# Shels_System_Bmduino.net
KiCad netlist of a schematic drawn in Altium Designer
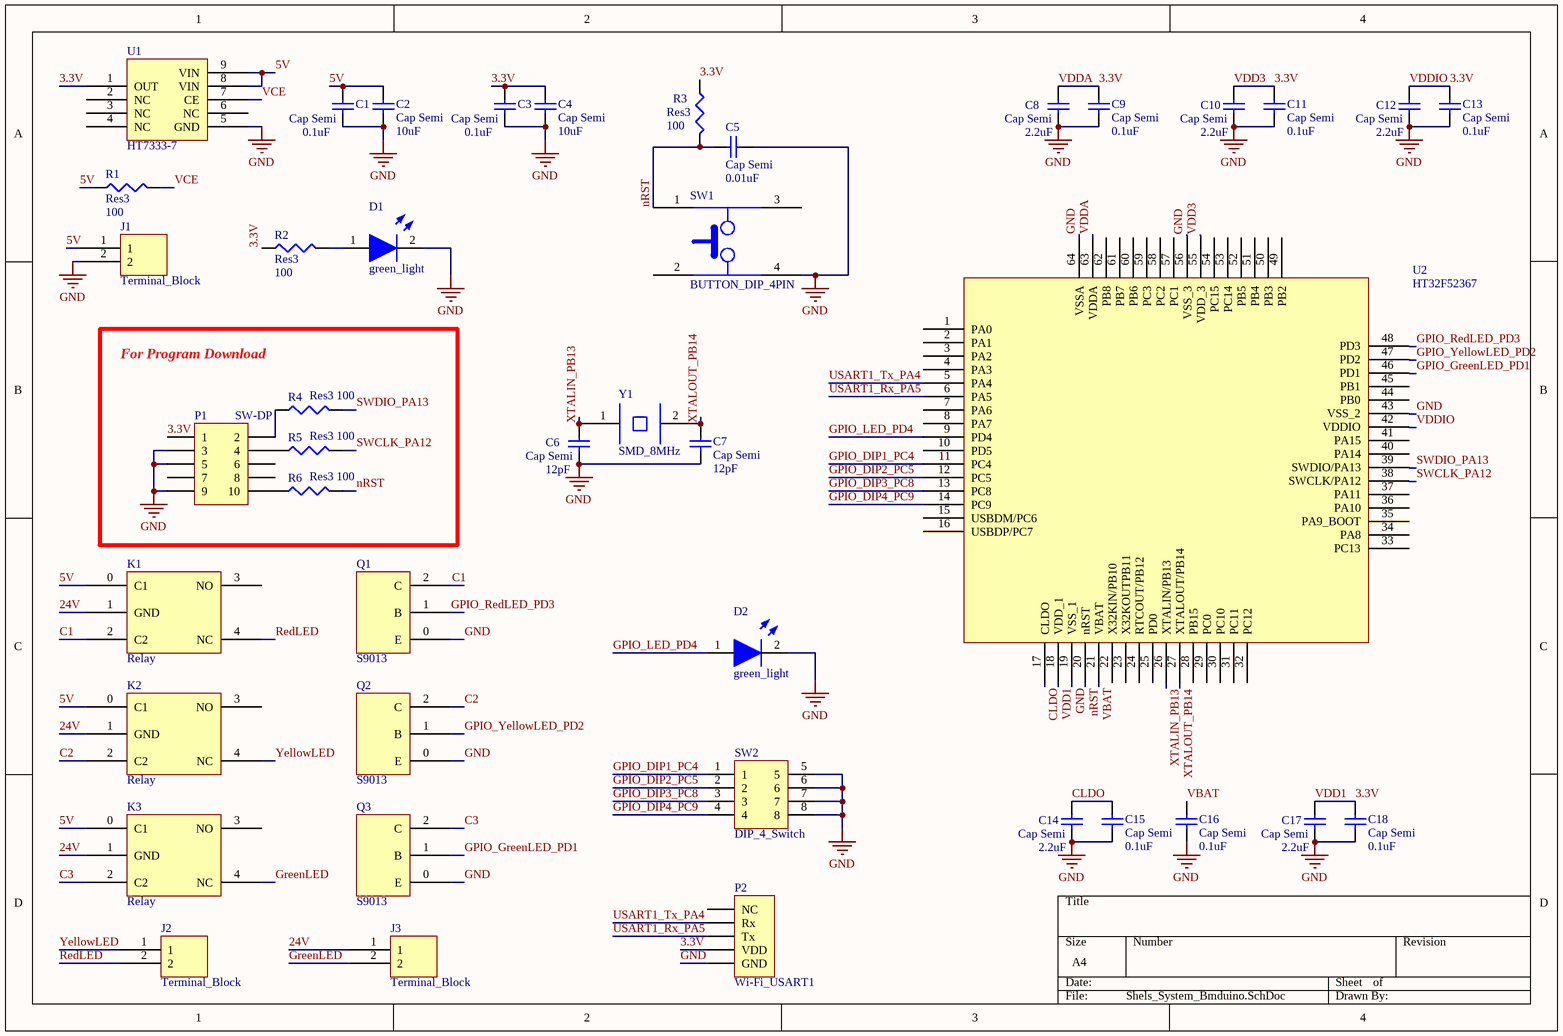
[diagram p0: Shels_System_Bmduino.SchDoc]

(export (version "E")
  (design (tool "Eeschema 10.0.6"))
  (components
    (comp (ref "C1")
      (value "Cap Semi")
      (footprint "1608[0603]")
      (description "Capacitor (Semiconductor SIM Model)")
      (fields (field (name "ALTIUM_VALUE") "0.1uF") (field (name "PUBLISHER") "Altium Limited"))
      (libsource (lib "Miscellaneous Devices") (part "Cap Semi"))
    )
    (comp (ref "C2")
      (value "Cap Semi")
      (footprint "1608[0603]")
      (description "Capacitor (Semiconductor SIM Model)")
      (fields (field (name "ALTIUM_VALUE") "10uF") (field (name "PUBLISHER") "Altium Limited"))
      (libsource (lib "Miscellaneous Devices") (part "Cap Semi"))
    )
    (comp (ref "C3")
      (value "Cap Semi")
      (footprint "1608[0603]")
      (description "Capacitor (Semiconductor SIM Model)")
      (fields (field (name "ALTIUM_VALUE") "0.1uF") (field (name "PUBLISHER") "Altium Limited"))
      (libsource (lib "Miscellaneous Devices") (part "Cap Semi"))
    )
    (comp (ref "C4")
      (value "Cap Semi")
      (footprint "1608[0603]")
      (description "Capacitor (Semiconductor SIM Model)")
      (fields (field (name "ALTIUM_VALUE") "10uF") (field (name "PUBLISHER") "Altium Limited"))
      (libsource (lib "Miscellaneous Devices") (part "Cap Semi"))
    )
    (comp (ref "C5")
      (value "Cap Semi")
      (footprint "1608[0603]")
      (description "Capacitor (Semiconductor SIM Model)")
      (fields (field (name "ALTIUM_VALUE") "0.01uF") (field (name "PUBLISHER") "Altium Limited"))
      (libsource (lib "Miscellaneous Devices") (part "Cap Semi"))
    )
    (comp (ref "C6")
      (value "Cap Semi")
      (footprint "1608[0603]")
      (description "Capacitor (Semiconductor SIM Model)")
      (fields (field (name "ALTIUM_VALUE") "12pF") (field (name "PUBLISHER") "Altium Limited"))
      (libsource (lib "Miscellaneous Devices") (part "Cap Semi"))
    )
    (comp (ref "C7")
      (value "Cap Semi")
      (footprint "1608[0603]")
      (description "Capacitor (Semiconductor SIM Model)")
      (fields (field (name "ALTIUM_VALUE") "12pF") (field (name "PUBLISHER") "Altium Limited"))
      (libsource (lib "Miscellaneous Devices") (part "Cap Semi"))
    )
    (comp (ref "C8")
      (value "Cap Semi")
      (footprint "1608[0603]")
      (description "Capacitor (Semiconductor SIM Model)")
      (fields (field (name "ALTIUM_VALUE") "2.2uF") (field (name "PUBLISHER") "Altium Limited"))
      (libsource (lib "Miscellaneous Devices") (part "Cap Semi"))
    )
    (comp (ref "C9")
      (value "Cap Semi")
      (footprint "1608[0603]")
      (description "Capacitor (Semiconductor SIM Model)")
      (fields (field (name "ALTIUM_VALUE") "0.1uF") (field (name "PUBLISHER") "Altium Limited"))
      (libsource (lib "Miscellaneous Devices") (part "Cap Semi"))
    )
    (comp (ref "C10")
      (value "Cap Semi")
      (footprint "1608[0603]")
      (description "Capacitor (Semiconductor SIM Model)")
      (fields (field (name "ALTIUM_VALUE") "2.2uF") (field (name "PUBLISHER") "Altium Limited"))
      (libsource (lib "Miscellaneous Devices") (part "Cap Semi"))
    )
    (comp (ref "C11")
      (value "Cap Semi")
      (footprint "1608[0603]")
      (description "Capacitor (Semiconductor SIM Model)")
      (fields (field (name "ALTIUM_VALUE") "0.1uF") (field (name "PUBLISHER") "Altium Limited"))
      (libsource (lib "Miscellaneous Devices") (part "Cap Semi"))
    )
    (comp (ref "C12")
      (value "Cap Semi")
      (footprint "1608[0603]")
      (description "Capacitor (Semiconductor SIM Model)")
      (fields (field (name "ALTIUM_VALUE") "2.2uF") (field (name "PUBLISHER") "Altium Limited"))
      (libsource (lib "Miscellaneous Devices") (part "Cap Semi"))
    )
    (comp (ref "C13")
      (value "Cap Semi")
      (footprint "1608[0603]")
      (description "Capacitor (Semiconductor SIM Model)")
      (fields (field (name "ALTIUM_VALUE") "0.1uF") (field (name "PUBLISHER") "Altium Limited"))
      (libsource (lib "Miscellaneous Devices") (part "Cap Semi"))
    )
    (comp (ref "C14")
      (value "Cap Semi")
      (footprint "1608[0603]")
      (description "Capacitor (Semiconductor SIM Model)")
      (fields (field (name "ALTIUM_VALUE") "2.2uF") (field (name "PUBLISHER") "Altium Limited"))
      (libsource (lib "Miscellaneous Devices") (part "Cap Semi"))
    )
    (comp (ref "C15")
      (value "Cap Semi")
      (footprint "1608[0603]")
      (description "Capacitor (Semiconductor SIM Model)")
      (fields (field (name "ALTIUM_VALUE") "0.1uF") (field (name "PUBLISHER") "Altium Limited"))
      (libsource (lib "Miscellaneous Devices") (part "Cap Semi"))
    )
    (comp (ref "C16")
      (value "Cap Semi")
      (footprint "1608[0603]")
      (description "Capacitor (Semiconductor SIM Model)")
      (fields (field (name "ALTIUM_VALUE") "0.1uF") (field (name "PUBLISHER") "Altium Limited"))
      (libsource (lib "Miscellaneous Devices") (part "Cap Semi"))
    )
    (comp (ref "C17")
      (value "Cap Semi")
      (footprint "1608[0603]")
      (description "Capacitor (Semiconductor SIM Model)")
      (fields (field (name "ALTIUM_VALUE") "2.2uF") (field (name "PUBLISHER") "Altium Limited"))
      (libsource (lib "Miscellaneous Devices") (part "Cap Semi"))
    )
    (comp (ref "C18")
      (value "Cap Semi")
      (footprint "1608[0603]")
      (description "Capacitor (Semiconductor SIM Model)")
      (fields (field (name "ALTIUM_VALUE") "0.1uF") (field (name "PUBLISHER") "Altium Limited"))
      (libsource (lib "Miscellaneous Devices") (part "Cap Semi"))
    )
    (comp (ref "D1")
      (value "green_light")
      (footprint "LED_Green")
      (libsource (lib "Lab_share") (part "LED_Green"))
    )
    (comp (ref "D2")
      (value "green_light")
      (footprint "LED_Green")
      (libsource (lib "Lab_share") (part "LED_Green"))
    )
    (comp (ref "J1")
      (value "Terminal_Block")
      (footprint "terminal block")
      (libsource (lib "Lab_share") (part "Terminal Block"))
    )
    (comp (ref "J2")
      (value "Terminal_Block")
      (footprint "terminal block")
      (libsource (lib "Lab_share") (part "Terminal Block"))
    )
    (comp (ref "J3")
      (value "Terminal_Block")
      (footprint "terminal block")
      (libsource (lib "Lab_share") (part "Terminal Block"))
    )
    (comp (ref "K1") (value "Relay") (footprint "Relay") (libsource (lib "Lab_share") (part "Relay")))
    (comp (ref "K2") (value "Relay") (footprint "Relay") (libsource (lib "Lab_share") (part "Relay")))
    (comp (ref "K3") (value "Relay") (footprint "Relay") (libsource (lib "Lab_share") (part "Relay")))
    (comp (ref "P1")
      (value "SW-DP")
      (footprint "HDR2X5")
      (description "Header, 5-Pin, Dual row")
      (fields (field (name "PUBLISHER") "Altium Limited"))
      (libsource (lib "Miscellaneous Connectors") (part "Header 5X2"))
    )
    (comp (ref "P2")
      (value "Wi-Fi_USART1")
      (footprint "HDR1X5")
      (description "Header, 5-Pin")
      (fields (field (name "PUBLISHER") "Altium Limited"))
      (libsource (lib "Miscellaneous Connectors") (part "Header 5"))
    )
    (comp (ref "Q1") (value "S9013") (footprint "S9013") (libsource (lib "Lab_share") (part "S9013")))
    (comp (ref "Q2") (value "S9013") (footprint "S9013") (libsource (lib "Lab_share") (part "S9013")))
    (comp (ref "Q3") (value "S9013") (footprint "S9013") (libsource (lib "Lab_share") (part "S9013")))
    (comp (ref "R1")
      (value "Res3")
      (footprint "J1-0603")
      (description "Resistor")
      (fields (field (name "ALTIUM_VALUE") "100") (field (name "PUBLISHER") "Altium Limited"))
      (libsource (lib "Miscellaneous Devices") (part "Res3"))
    )
    (comp (ref "R2")
      (value "Res3")
      (footprint "J1-0603")
      (description "Resistor")
      (fields (field (name "ALTIUM_VALUE") "100") (field (name "PUBLISHER") "Altium Limited"))
      (libsource (lib "Miscellaneous Devices") (part "Res3"))
    )
    (comp (ref "R3")
      (value "Res3")
      (footprint "J1-0603")
      (description "Resistor")
      (fields (field (name "ALTIUM_VALUE") "100") (field (name "PUBLISHER") "Altium Limited"))
      (libsource (lib "Miscellaneous Devices") (part "Res3"))
    )
    (comp (ref "R4")
      (value "Res3")
      (footprint "J1-0603")
      (description "Resistor")
      (fields (field (name "ALTIUM_VALUE") "100") (field (name "PUBLISHER") "Altium Limited"))
      (libsource (lib "Miscellaneous Devices") (part "Res3"))
    )
    (comp (ref "R5")
      (value "Res3")
      (footprint "J1-0603")
      (description "Resistor")
      (fields (field (name "ALTIUM_VALUE") "100") (field (name "PUBLISHER") "Altium Limited"))
      (libsource (lib "Miscellaneous Devices") (part "Res3"))
    )
    (comp (ref "R6")
      (value "Res3")
      (footprint "J1-0603")
      (description "Resistor")
      (fields (field (name "ALTIUM_VALUE") "100") (field (name "PUBLISHER") "Altium Limited"))
      (libsource (lib "Miscellaneous Devices") (part "Res3"))
    )
    (comp (ref "SW1")
      (value "BUTTON_DIP_4PIN")
      (footprint "Push_Button")
      (libsource (lib "Lab_share") (part "Push_Button"))
    )
    (comp (ref "SW2")
      (value "DIP_4_Switch")
      (footprint "D_Switch_4")
      (libsource (lib "Lab_share") (part "Switch_D_4"))
    )
    (comp (ref "U1") (value "HT7333-7") (footprint "HT7333") (libsource (lib "Lab_share") (part "HT7333")))
    (comp (ref "U2")
      (value "HT32F52367")
      (footprint "HT32H52367")
      (libsource (lib "Lab_share") (part "HT32F52367"))
    )
    (comp (ref "Y1")
      (value "SMD_8MHz")
      (footprint "Quartz-Crystal-8MHz")
      (libsource (lib "Lab_share") (part "Quartz_Crystal_8MHz"))
    )
  )
  (nets
    (net (code "1") (name "/3.3V") (class "Default")
      (node (ref "C10") (pin "1") (pinfunction "1_1") (pintype "passive"))
      (node (ref "C11") (pin "2") (pinfunction "2_2") (pintype "passive"))
      (node (ref "C12") (pin "1") (pinfunction "1_1") (pintype "passive"))
      (node (ref "C13") (pin "2") (pinfunction "2_2") (pintype "passive"))
      (node (ref "C17") (pin "1") (pinfunction "1_1") (pintype "passive"))
      (node (ref "C18") (pin "2") (pinfunction "2_2") (pintype "passive"))
      (node (ref "C3") (pin "2") (pinfunction "2_2") (pintype "passive"))
      (node (ref "C4") (pin "2") (pinfunction "2_2") (pintype "passive"))
      (node (ref "C8") (pin "1") (pinfunction "1_1") (pintype "passive"))
      (node (ref "C9") (pin "2") (pinfunction "2_2") (pintype "passive"))
      (node (ref "P1") (pin "1") (pinfunction "1_1") (pintype "passive"))
      (node (ref "P2") (pin "4") (pinfunction "VDD_4") (pintype "passive"))
      (node (ref "R2") (pin "1") (pinfunction "1_1") (pintype "passive"))
      (node (ref "R3") (pin "1") (pinfunction "1_1") (pintype "passive"))
      (node (ref "U1") (pin "1") (pinfunction "OUT_1") (pintype "passive"))
      (node (ref "U2") (pin "18") (pinfunction "VDD_1_18") (pintype "passive"))
      (node (ref "U2") (pin "42") (pinfunction "VDDIO_42") (pintype "passive"))
      (node (ref "U2") (pin "55") (pinfunction "VDD_3_55") (pintype "passive"))
      (node (ref "U2") (pin "63") (pinfunction "VDDA_63") (pintype "passive"))
    )
    (net (code "2") (name "/5V") (class "Default")
      (node (ref "C1") (pin "2") (pinfunction "2_2") (pintype "passive"))
      (node (ref "C2") (pin "2") (pinfunction "2_2") (pintype "passive"))
      (node (ref "J1") (pin "1") (pinfunction "1_1") (pintype "passive"))
      (node (ref "K1") (pin "0") (pinfunction "C1_0") (pintype "passive"))
      (node (ref "K2") (pin "0") (pinfunction "C1_0") (pintype "passive"))
      (node (ref "K3") (pin "0") (pinfunction "C1_0") (pintype "passive"))
      (node (ref "R1") (pin "1") (pinfunction "1_1") (pintype "passive"))
      (node (ref "U1") (pin "8") (pinfunction "VIN_8") (pintype "passive"))
      (node (ref "U1") (pin "9") (pinfunction "VIN_9") (pintype "passive"))
    )
    (net (code "3") (name "/24V") (class "Default")
      (node (ref "J3") (pin "1") (pinfunction "1_1") (pintype "passive"))
      (node (ref "K1") (pin "1") (pinfunction "GND_1") (pintype "passive"))
      (node (ref "K2") (pin "1") (pinfunction "GND_1") (pintype "passive"))
      (node (ref "K3") (pin "1") (pinfunction "GND_1") (pintype "passive"))
    )
    (net (code "4") (name "/C1") (class "Default")
      (node (ref "K1") (pin "2") (pinfunction "C2_2") (pintype "passive"))
      (node (ref "Q1") (pin "2") (pinfunction "C_2") (pintype "passive"))
    )
    (net (code "5") (name "/C2") (class "Default")
      (node (ref "K2") (pin "2") (pinfunction "C2_2") (pintype "passive"))
      (node (ref "Q2") (pin "2") (pinfunction "C_2") (pintype "passive"))
    )
    (net (code "6") (name "/C3") (class "Default")
      (node (ref "K3") (pin "2") (pinfunction "C2_2") (pintype "passive"))
      (node (ref "Q3") (pin "2") (pinfunction "C_2") (pintype "passive"))
    )
    (net (code "7") (name "/CLDO") (class "Default")
      (node (ref "C14") (pin "1") (pinfunction "1_1") (pintype "passive"))
      (node (ref "C15") (pin "2") (pinfunction "2_2") (pintype "passive"))
      (node (ref "U2") (pin "17") (pinfunction "CLDO_17") (pintype "passive"))
    )
    (net (code "8") (name "/GPIO_DIP1_PC4") (class "Default")
      (node (ref "SW2") (pin "1") (pinfunction "1_1") (pintype "passive"))
      (node (ref "U2") (pin "11") (pinfunction "PC4_11") (pintype "passive"))
    )
    (net (code "9") (name "/GPIO_DIP2_PC5") (class "Default")
      (node (ref "SW2") (pin "2") (pinfunction "2_2") (pintype "passive"))
      (node (ref "U2") (pin "12") (pinfunction "PC5_12") (pintype "passive"))
    )
    (net (code "10") (name "/GPIO_DIP3_PC8") (class "Default")
      (node (ref "SW2") (pin "3") (pinfunction "3_3") (pintype "passive"))
      (node (ref "U2") (pin "13") (pinfunction "PC8_13") (pintype "passive"))
    )
    (net (code "11") (name "/GPIO_DIP4_PC9") (class "Default")
      (node (ref "SW2") (pin "4") (pinfunction "4_4") (pintype "passive"))
      (node (ref "U2") (pin "14") (pinfunction "PC9_14") (pintype "passive"))
    )
    (net (code "12") (name "/GPIO_GreenLED_PD1") (class "Default")
      (node (ref "Q3") (pin "1") (pinfunction "B_1") (pintype "passive"))
      (node (ref "U2") (pin "46") (pinfunction "PD1_46") (pintype "passive"))
    )
    (net (code "13") (name "/GPIO_LED_PD4") (class "Default")
      (node (ref "D2") (pin "1") (pintype "passive"))
      (node (ref "U2") (pin "9") (pinfunction "PD4_9") (pintype "passive"))
    )
    (net (code "14") (name "/GPIO_RedLED_PD3") (class "Default")
      (node (ref "Q1") (pin "1") (pinfunction "B_1") (pintype "passive"))
      (node (ref "U2") (pin "48") (pinfunction "PD3_48") (pintype "passive"))
    )
    (net (code "15") (name "/GPIO_YellowLED_PD2") (class "Default")
      (node (ref "Q2") (pin "1") (pinfunction "B_1") (pintype "passive"))
      (node (ref "U2") (pin "47") (pinfunction "PD2_47") (pintype "passive"))
    )
    (net (code "16") (name "/GreenLED") (class "Default")
      (node (ref "J3") (pin "2") (pinfunction "2_2") (pintype "passive"))
      (node (ref "K3") (pin "4") (pinfunction "NC_4") (pintype "passive"))
    )
    (net (code "17") (name "/RedLED") (class "Default")
      (node (ref "J2") (pin "2") (pinfunction "2_2") (pintype "passive"))
      (node (ref "K1") (pin "4") (pinfunction "NC_4") (pintype "passive"))
    )
    (net (code "18") (name "/SWCLK_PA12") (class "Default")
      (node (ref "R5") (pin "2") (pinfunction "2_2") (pintype "passive"))
      (node (ref "U2") (pin "38") (pinfunction "SWCLK/PA12_38") (pintype "passive"))
    )
    (net (code "19") (name "/SWDIO_PA13") (class "Default")
      (node (ref "R4") (pin "2") (pinfunction "2_2") (pintype "passive"))
      (node (ref "U2") (pin "39") (pinfunction "SWDIO/PA13_39") (pintype "passive"))
    )
    (net (code "20") (name "/USART1_Rx_PA5") (class "Default")
      (node (ref "P2") (pin "3") (pinfunction "Tx_3") (pintype "passive"))
      (node (ref "U2") (pin "6") (pinfunction "PA5_6") (pintype "passive"))
    )
    (net (code "21") (name "/USART1_Tx_PA4") (class "Default")
      (node (ref "P2") (pin "2") (pinfunction "Rx_2") (pintype "passive"))
      (node (ref "U2") (pin "5") (pinfunction "PA4_5") (pintype "passive"))
    )
    (net (code "22") (name "/VBAT") (class "Default")
      (node (ref "C16") (pin "2") (pinfunction "2_2") (pintype "passive"))
      (node (ref "U2") (pin "21") (pinfunction "VBAT_21") (pintype "passive"))
    )
    (net (code "23") (name "/VCE") (class "Default")
      (node (ref "R1") (pin "2") (pinfunction "2_2") (pintype "passive"))
      (node (ref "U1") (pin "7") (pinfunction "CE_7") (pintype "passive"))
    )
    (net (code "24") (name "/XTALIN_PB13") (class "Default")
      (node (ref "C6") (pin "1") (pinfunction "1_1") (pintype "passive"))
      (node (ref "U2") (pin "26") (pinfunction "XTALIN/PB13_26") (pintype "passive"))
      (node (ref "Y1") (pin "1") (pintype "passive"))
    )
    (net (code "25") (name "/XTALOUT_PB14") (class "Default")
      (node (ref "C7") (pin "2") (pinfunction "2_2") (pintype "passive"))
      (node (ref "U2") (pin "27") (pinfunction "XTALOUT/PB14_27") (pintype "passive"))
      (node (ref "Y1") (pin "2") (pintype "passive"))
    )
    (net (code "26") (name "/YellowLED") (class "Default")
      (node (ref "J2") (pin "1") (pinfunction "1_1") (pintype "passive"))
      (node (ref "K2") (pin "4") (pinfunction "NC_4") (pintype "passive"))
    )
    (net (code "27") (name "/nRST") (class "Default")
      (node (ref "C5") (pin "2") (pinfunction "2_2") (pintype "passive"))
      (node (ref "R3") (pin "2") (pinfunction "2_2") (pintype "passive"))
      (node (ref "R6") (pin "2") (pinfunction "2_2") (pintype "passive"))
      (node (ref "SW1") (pin "1") (pintype "passive"))
      (node (ref "U2") (pin "20") (pinfunction "nRST_20") (pintype "passive"))
    )
    (net (code "28") (name "GND") (class "Default")
      (node (ref "C1") (pin "1") (pinfunction "1_1") (pintype "passive"))
      (node (ref "C10") (pin "2") (pinfunction "2_2") (pintype "passive"))
      (node (ref "C11") (pin "1") (pinfunction "1_1") (pintype "passive"))
      (node (ref "C12") (pin "2") (pinfunction "2_2") (pintype "passive"))
      (node (ref "C13") (pin "1") (pinfunction "1_1") (pintype "passive"))
      (node (ref "C14") (pin "2") (pinfunction "2_2") (pintype "passive"))
      (node (ref "C15") (pin "1") (pinfunction "1_1") (pintype "passive"))
      (node (ref "C16") (pin "1") (pinfunction "1_1") (pintype "passive"))
      (node (ref "C17") (pin "2") (pinfunction "2_2") (pintype "passive"))
      (node (ref "C18") (pin "1") (pinfunction "1_1") (pintype "passive"))
      (node (ref "C2") (pin "1") (pinfunction "1_1") (pintype "passive"))
      (node (ref "C3") (pin "1") (pinfunction "1_1") (pintype "passive"))
      (node (ref "C4") (pin "1") (pinfunction "1_1") (pintype "passive"))
      (node (ref "C5") (pin "1") (pinfunction "1_1") (pintype "passive"))
      (node (ref "C6") (pin "2") (pinfunction "2_2") (pintype "passive"))
      (node (ref "C7") (pin "1") (pinfunction "1_1") (pintype "passive"))
      (node (ref "C8") (pin "2") (pinfunction "2_2") (pintype "passive"))
      (node (ref "C9") (pin "1") (pinfunction "1_1") (pintype "passive"))
      (node (ref "D1") (pin "2") (pintype "passive"))
      (node (ref "D2") (pin "2") (pintype "passive"))
      (node (ref "J1") (pin "2") (pinfunction "2_2") (pintype "passive"))
      (node (ref "P1") (pin "3") (pinfunction "3_3") (pintype "passive"))
      (node (ref "P1") (pin "5") (pinfunction "5_5") (pintype "passive"))
      (node (ref "P1") (pin "9") (pinfunction "9_9") (pintype "passive"))
      (node (ref "P2") (pin "5") (pinfunction "GND_5") (pintype "passive"))
      (node (ref "Q1") (pin "0") (pinfunction "E_0") (pintype "passive"))
      (node (ref "Q2") (pin "0") (pinfunction "E_0") (pintype "passive"))
      (node (ref "Q3") (pin "0") (pinfunction "E_0") (pintype "passive"))
      (node (ref "SW1") (pin "4") (pintype "passive"))
      (node (ref "SW2") (pin "5") (pinfunction "5_5") (pintype "passive"))
      (node (ref "SW2") (pin "6") (pinfunction "6_6") (pintype "passive"))
      (node (ref "SW2") (pin "7") (pinfunction "7_7") (pintype "passive"))
      (node (ref "SW2") (pin "8") (pinfunction "8_8") (pintype "passive"))
      (node (ref "U1") (pin "5") (pinfunction "GND_5") (pintype "passive"))
      (node (ref "U2") (pin "19") (pinfunction "VSS_1_19") (pintype "passive"))
      (node (ref "U2") (pin "43") (pinfunction "VSS_2_43") (pintype "passive"))
      (node (ref "U2") (pin "56") (pinfunction "VSS_3_56") (pintype "passive"))
      (node (ref "U2") (pin "64") (pinfunction "VSSA_64") (pintype "passive"))
    )
    (net (code "29") (name "Net-(D1-Pad1)") (class "Default")
      (node (ref "D1") (pin "1") (pintype "passive"))
      (node (ref "R2") (pin "2") (pinfunction "2_2") (pintype "passive"))
    )
    (net (code "30") (name "Net-(P1-Pad2)") (class "Default")
      (node (ref "P1") (pin "2") (pinfunction "2_2") (pintype "passive"))
      (node (ref "R4") (pin "1") (pinfunction "1_1") (pintype "passive"))
    )
    (net (code "31") (name "Net-(P1-Pad4)") (class "Default")
      (node (ref "P1") (pin "4") (pinfunction "4_4") (pintype "passive"))
      (node (ref "R5") (pin "1") (pinfunction "1_1") (pintype "passive"))
    )
    (net (code "32") (name "Net-(P1-Pad10)") (class "Default")
      (node (ref "P1") (pin "10") (pinfunction "10_10") (pintype "passive"))
      (node (ref "R6") (pin "1") (pinfunction "1_1") (pintype "passive"))
    )
    (net (code "33") (name "unconnected-(K1-NO-Pad3)") (class "Default")
      (node (ref "K1") (pin "3") (pinfunction "NO_3") (pintype "passive"))
    )
    (net (code "34") (name "unconnected-(K2-NO-Pad3)") (class "Default")
      (node (ref "K2") (pin "3") (pinfunction "NO_3") (pintype "passive"))
    )
    (net (code "35") (name "unconnected-(K3-NO-Pad3)") (class "Default")
      (node (ref "K3") (pin "3") (pinfunction "NO_3") (pintype "passive"))
    )
    (net (code "36") (name "unconnected-(P1-Pad6)") (class "Default")
      (node (ref "P1") (pin "6") (pinfunction "6_6") (pintype "passive"))
    )
    (net (code "37") (name "unconnected-(P1-Pad7)") (class "Default")
      (node (ref "P1") (pin "7") (pinfunction "7_7") (pintype "passive"))
    )
    (net (code "38") (name "unconnected-(P1-Pad8)") (class "Default")
      (node (ref "P1") (pin "8") (pinfunction "8_8") (pintype "passive"))
    )
    (net (code "39") (name "unconnected-(P2-NC-Pad1)") (class "Default")
      (node (ref "P2") (pin "1") (pinfunction "NC_1") (pintype "passive"))
    )
    (net (code "40") (name "unconnected-(SW1-Pad2)") (class "Default")
      (node (ref "SW1") (pin "2") (pintype "passive"))
    )
    (net (code "41") (name "unconnected-(SW1-Pad3)") (class "Default")
      (node (ref "SW1") (pin "3") (pintype "passive"))
    )
    (net (code "42") (name "unconnected-(U1-NC-Pad2)") (class "Default")
      (node (ref "U1") (pin "2") (pinfunction "NC_2") (pintype "passive"))
    )
    (net (code "43") (name "unconnected-(U1-NC-Pad3)") (class "Default")
      (node (ref "U1") (pin "3") (pinfunction "NC_3") (pintype "passive"))
    )
    (net (code "44") (name "unconnected-(U1-NC-Pad4)") (class "Default")
      (node (ref "U1") (pin "4") (pinfunction "NC_4") (pintype "passive"))
    )
    (net (code "45") (name "unconnected-(U1-NC-Pad6)") (class "Default")
      (node (ref "U1") (pin "6") (pinfunction "NC_6") (pintype "passive"))
    )
    (net (code "46") (name "unconnected-(U2-PA0-Pad1)") (class "Default")
      (node (ref "U2") (pin "1") (pinfunction "PA0_1") (pintype "passive"))
    )
    (net (code "47") (name "unconnected-(U2-PA1-Pad2)") (class "Default")
      (node (ref "U2") (pin "2") (pinfunction "PA1_2") (pintype "passive"))
    )
    (net (code "48") (name "unconnected-(U2-PA2-Pad3)") (class "Default")
      (node (ref "U2") (pin "3") (pinfunction "PA2_3") (pintype "passive"))
    )
    (net (code "49") (name "unconnected-(U2-PA3-Pad4)") (class "Default")
      (node (ref "U2") (pin "4") (pinfunction "PA3_4") (pintype "passive"))
    )
    (net (code "50") (name "unconnected-(U2-PA6-Pad7)") (class "Default")
      (node (ref "U2") (pin "7") (pinfunction "PA6_7") (pintype "passive"))
    )
    (net (code "51") (name "unconnected-(U2-PA7-Pad8)") (class "Default")
      (node (ref "U2") (pin "8") (pinfunction "PA7_8") (pintype "passive"))
    )
    (net (code "52") (name "unconnected-(U2-PA8-Pad34)") (class "Default")
      (node (ref "U2") (pin "34") (pinfunction "PA8_34") (pintype "passive"))
    )
    (net (code "53") (name "unconnected-(U2-PA9_BOOT-Pad35)") (class "Default")
      (node (ref "U2") (pin "35") (pinfunction "PA9_BOOT_35") (pintype "passive"))
    )
    (net (code "54") (name "unconnected-(U2-PA10-Pad36)") (class "Default")
      (node (ref "U2") (pin "36") (pinfunction "PA10_36") (pintype "passive"))
    )
    (net (code "55") (name "unconnected-(U2-PA11-Pad37)") (class "Default")
      (node (ref "U2") (pin "37") (pinfunction "PA11_37") (pintype "passive"))
    )
    (net (code "56") (name "unconnected-(U2-PA14-Pad40)") (class "Default")
      (node (ref "U2") (pin "40") (pinfunction "PA14_40") (pintype "passive"))
    )
    (net (code "57") (name "unconnected-(U2-PA15-Pad41)") (class "Default")
      (node (ref "U2") (pin "41") (pinfunction "PA15_41") (pintype "passive"))
    )
    (net (code "58") (name "unconnected-(U2-PB0-Pad44)") (class "Default")
      (node (ref "U2") (pin "44") (pinfunction "PB0_44") (pintype "passive"))
    )
    (net (code "59") (name "unconnected-(U2-PB1-Pad45)") (class "Default")
      (node (ref "U2") (pin "45") (pinfunction "PB1_45") (pintype "passive"))
    )
    (net (code "60") (name "unconnected-(U2-PB2-Pad49)") (class "Default")
      (node (ref "U2") (pin "49") (pinfunction "PB2_49") (pintype "passive"))
    )
    (net (code "61") (name "unconnected-(U2-PB3-Pad50)") (class "Default")
      (node (ref "U2") (pin "50") (pinfunction "PB3_50") (pintype "passive"))
    )
    (net (code "62") (name "unconnected-(U2-PB4-Pad51)") (class "Default")
      (node (ref "U2") (pin "51") (pinfunction "PB4_51") (pintype "passive"))
    )
    (net (code "63") (name "unconnected-(U2-PB5-Pad52)") (class "Default")
      (node (ref "U2") (pin "52") (pinfunction "PB5_52") (pintype "passive"))
    )
    (net (code "64") (name "unconnected-(U2-PB6-Pad60)") (class "Default")
      (node (ref "U2") (pin "60") (pinfunction "PB6_60") (pintype "passive"))
    )
    (net (code "65") (name "unconnected-(U2-PB7-Pad61)") (class "Default")
      (node (ref "U2") (pin "61") (pinfunction "PB7_61") (pintype "passive"))
    )
    (net (code "66") (name "unconnected-(U2-PB8-Pad62)") (class "Default")
      (node (ref "U2") (pin "62") (pinfunction "PB8_62") (pintype "passive"))
    )
    (net (code "67") (name "unconnected-(U2-PB15-Pad28)") (class "Default")
      (node (ref "U2") (pin "28") (pinfunction "PB15_28") (pintype "passive"))
    )
    (net (code "68") (name "unconnected-(U2-PC0-Pad29)") (class "Default")
      (node (ref "U2") (pin "29") (pinfunction "PC0_29") (pintype "passive"))
    )
    (net (code "69") (name "unconnected-(U2-PC1-Pad57)") (class "Default")
      (node (ref "U2") (pin "57") (pinfunction "PC1_57") (pintype "passive"))
    )
    (net (code "70") (name "unconnected-(U2-PC2-Pad58)") (class "Default")
      (node (ref "U2") (pin "58") (pinfunction "PC2_58") (pintype "passive"))
    )
    (net (code "71") (name "unconnected-(U2-PC3-Pad59)") (class "Default")
      (node (ref "U2") (pin "59") (pinfunction "PC3_59") (pintype "passive"))
    )
    (net (code "72") (name "unconnected-(U2-PC10-Pad30)") (class "Default")
      (node (ref "U2") (pin "30") (pinfunction "PC10_30") (pintype "passive"))
    )
    (net (code "73") (name "unconnected-(U2-PC11-Pad31)") (class "Default")
      (node (ref "U2") (pin "31") (pinfunction "PC11_31") (pintype "passive"))
    )
    (net (code "74") (name "unconnected-(U2-PC12-Pad32)") (class "Default")
      (node (ref "U2") (pin "32") (pinfunction "PC12_32") (pintype "passive"))
    )
    (net (code "75") (name "unconnected-(U2-PC13-Pad33)") (class "Default")
      (node (ref "U2") (pin "33") (pinfunction "PC13_33") (pintype "passive"))
    )
    (net (code "76") (name "unconnected-(U2-PC14-Pad53)") (class "Default")
      (node (ref "U2") (pin "53") (pinfunction "PC14_53") (pintype "passive"))
    )
    (net (code "77") (name "unconnected-(U2-PC15-Pad54)") (class "Default")
      (node (ref "U2") (pin "54") (pinfunction "PC15_54") (pintype "passive"))
    )
    (net (code "78") (name "unconnected-(U2-PD0-Pad25)") (class "Default")
      (node (ref "U2") (pin "25") (pinfunction "PD0_25") (pintype "passive"))
    )
    (net (code "79") (name "unconnected-(U2-PD5-Pad10)") (class "Default")
      (node (ref "U2") (pin "10") (pinfunction "PD5_10") (pintype "passive"))
    )
    (net (code "80") (name "unconnected-(U2-RTCOUT{slash}PB12-Pad24)") (class "Default")
      (node (ref "U2") (pin "24") (pinfunction "RTCOUT/PB12_24") (pintype "passive"))
    )
    (net (code "81") (name "unconnected-(U2-USBDM{slash}PC6-Pad15)") (class "Default")
      (node (ref "U2") (pin "15") (pinfunction "USBDM/PC6_15") (pintype "passive"))
    )
    (net (code "82") (name "unconnected-(U2-USBDP{slash}PC7-Pad16)") (class "Default")
      (node (ref "U2") (pin "16") (pinfunction "USBDP/PC7_16") (pintype "passive"))
    )
    (net (code "83") (name "unconnected-(U2-X32KIN{slash}PB10-Pad22)") (class "Default")
      (node (ref "U2") (pin "22") (pinfunction "X32KIN/PB10_22") (pintype "passive"))
    )
    (net (code "84") (name "unconnected-(U2-X32KOUTPB11-Pad23)") (class "Default")
      (node (ref "U2") (pin "23") (pinfunction "X32KOUTPB11_23") (pintype "passive"))
    )
  )
)
